# Testing_LAB_EMG_V1_2.net
KiCad netlist of a schematic drawn in EAGLE
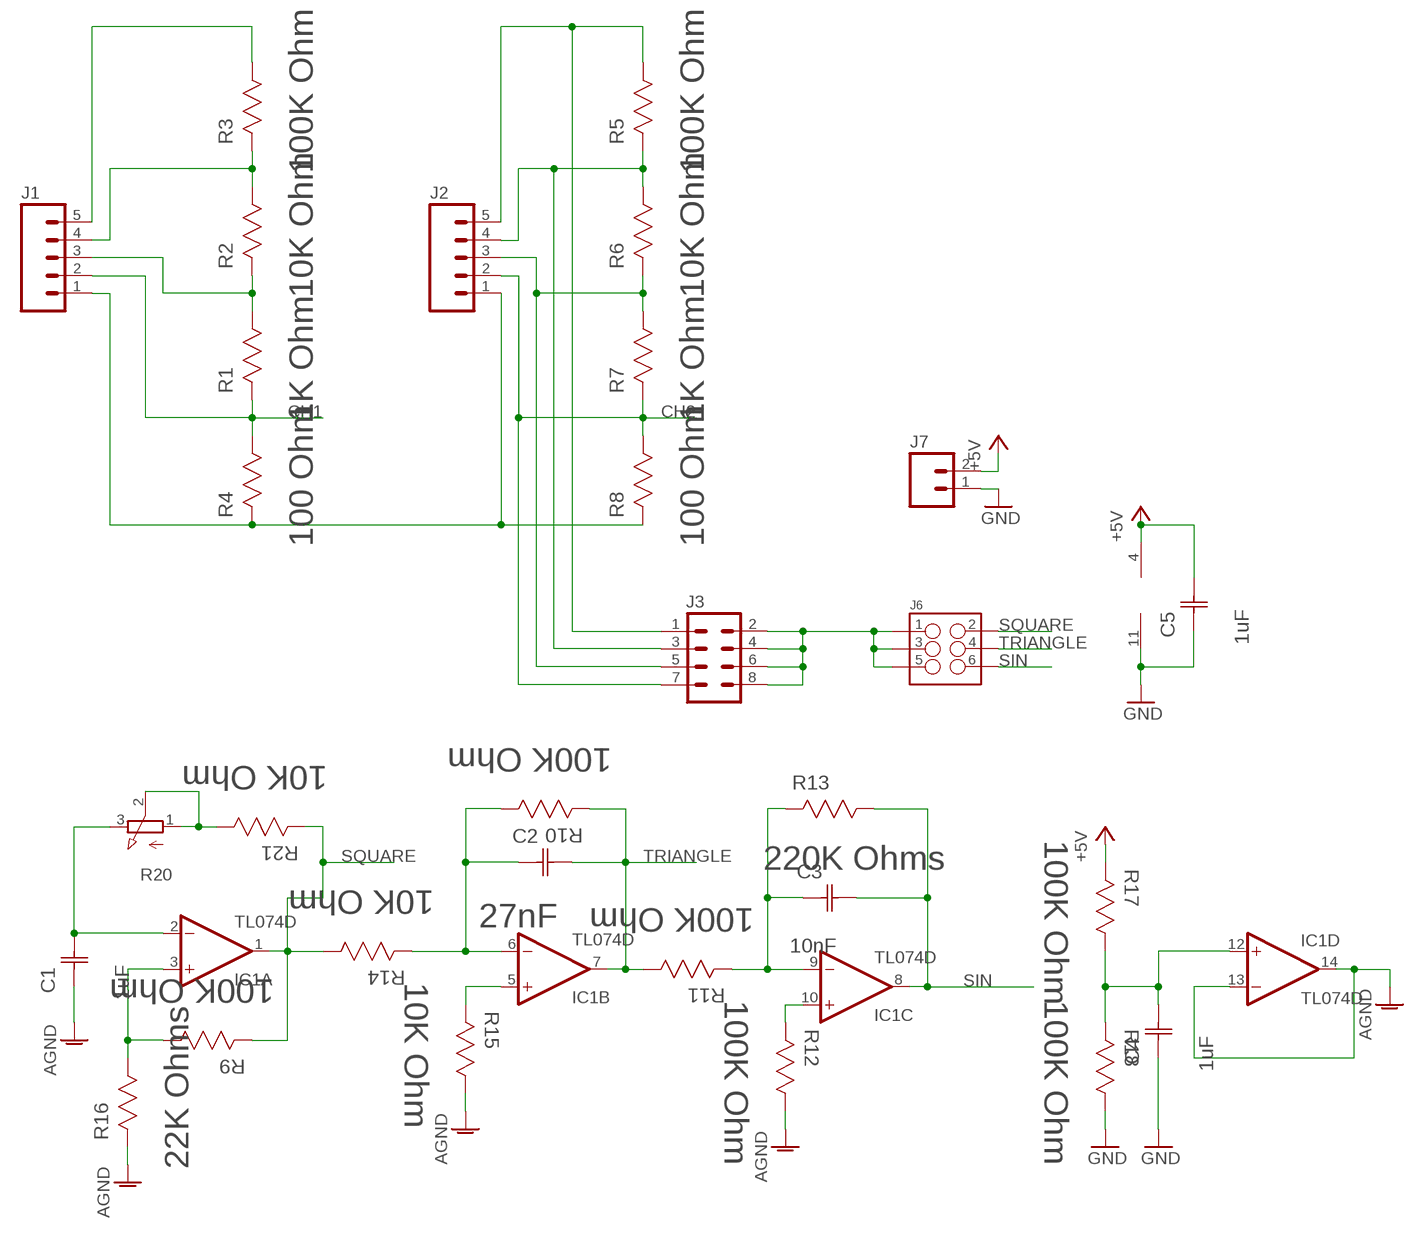
[diagram p0: schematic, sheet 1]

(export (version "E")
  (design (tool "Eeschema 10.0.6"))
  (components
    (comp (ref "C1")
      (value "1uF")
      (footprint "eagle-import:CAPC1608X94N")
      (fields (field (name "MPN") "0603YC105KAT2A") (field (name "TOLERANCE") "±10%"))
      (libsource (lib "eagle-import") (part "0603YC105KAT2A"))
    )
    (comp (ref "C2")
      (value "27nF")
      (footprint "eagle-import:CAPC1005X60N")
      (fields (field (name "MPN") "C0402C273K3RACTU") (field (name "TOLERANCE") "±10%"))
      (libsource (lib "eagle-import") (part "C0402C273K3RACTU"))
    )
    (comp (ref "C3")
      (value "10nF")
      (footprint "eagle-import:CAPC1608X90N")
      (fields (field (name "MPN") "06031C103KAT2A") (field (name "TOLERANCE") "±10%"))
      (libsource (lib "eagle-import") (part "06031C103KAT2A"))
    )
    (comp (ref "C4")
      (value "1uF")
      (footprint "eagle-import:CAPC1608X94N")
      (fields (field (name "MPN") "0603YC105KAT2A") (field (name "TOLERANCE") "±10%"))
      (libsource (lib "eagle-import") (part "0603YC105KAT2A"))
    )
    (comp (ref "C5")
      (value "1uF")
      (footprint "eagle-import:CAPC1608X94N")
      (fields (field (name "MPN") "0603YC105KAT2A") (field (name "TOLERANCE") "±10%"))
      (libsource (lib "eagle-import") (part "0603YC105KAT2A"))
    )
    (comp (ref "IC1")
      (value "TL074D")
      (footprint "eagle-import:SO14")
      (libsource (lib "eagle-import") (part "TL074D"))
    )
    (comp (ref "J1")
      (value "M05PTH")
      (footprint "eagle-import:1X05")
      (libsource (lib "eagle-import") (part "M05PTH"))
    )
    (comp (ref "J2")
      (value "M05PTH")
      (footprint "eagle-import:1X05")
      (libsource (lib "eagle-import") (part "M05PTH"))
    )
    (comp (ref "J3")
      (value "M04X2")
      (footprint "eagle-import:2X4")
      (libsource (lib "eagle-import") (part "M04X2"))
    )
    (comp (ref "J6")
      (value "M03X2NO_SILK")
      (footprint "eagle-import:2X3-NS")
      (libsource (lib "eagle-import") (part "M03X2NO_SILK"))
    )
    (comp (ref "J7")
      (value "M02PTH")
      (footprint "eagle-import:1X02")
      (libsource (lib "eagle-import") (part "M02PTH"))
    )
    (comp (ref "R1")
      (value "1K Ohm")
      (footprint "eagle-import:RESC1608X60N")
      (fields (field (name "MPN") "9C06031A1001FKHFT") (field (name "TOLERANCE") "±1%"))
      (libsource (lib "eagle-import") (part "9C06031A1001FKHFT"))
    )
    (comp (ref "R2")
      (value "10K Ohm")
      (footprint "eagle-import:RESC1608X60N")
      (fields (field (name "MPN") "9C06031A1002JLHFT") (field (name "TOLERANCE") "±5%"))
      (libsource (lib "eagle-import") (part "9C06031A1002JLHFT"))
    )
    (comp (ref "R3")
      (value "100K Ohm")
      (footprint "eagle-import:RESC1608X60N")
      (fields (field (name "MPN") "9C06031A1003FKHFT") (field (name "TOLERANCE") "±1%"))
      (libsource (lib "eagle-import") (part "9C06031A1003FKHFT"))
    )
    (comp (ref "R4")
      (value "100 Ohm")
      (footprint "eagle-import:RESC1608X60N")
      (fields (field (name "MPN") "9C06031A1000JLHFT") (field (name "TOLERANCE") "±5%"))
      (libsource (lib "eagle-import") (part "9C06031A1000JLHFT"))
    )
    (comp (ref "R5")
      (value "100K Ohm")
      (footprint "eagle-import:RESC1608X60N")
      (fields (field (name "MPN") "9C06031A1003FKHFT") (field (name "TOLERANCE") "±1%"))
      (libsource (lib "eagle-import") (part "9C06031A1003FKHFT"))
    )
    (comp (ref "R6")
      (value "10K Ohm")
      (footprint "eagle-import:RESC1608X60N")
      (fields (field (name "MPN") "9C06031A1002JLHFT") (field (name "TOLERANCE") "±5%"))
      (libsource (lib "eagle-import") (part "9C06031A1002JLHFT"))
    )
    (comp (ref "R7")
      (value "1K Ohm")
      (footprint "eagle-import:RESC1608X60N")
      (fields (field (name "MPN") "9C06031A1001FKHFT") (field (name "TOLERANCE") "±1%"))
      (libsource (lib "eagle-import") (part "9C06031A1001FKHFT"))
    )
    (comp (ref "R8")
      (value "100 Ohm")
      (footprint "eagle-import:RESC1608X60N")
      (fields (field (name "MPN") "9C06031A1000JLHFT") (field (name "TOLERANCE") "±5%"))
      (libsource (lib "eagle-import") (part "9C06031A1000JLHFT"))
    )
    (comp (ref "R9")
      (value "100K Ohm")
      (footprint "eagle-import:RESC1608X60N")
      (fields (field (name "MPN") "9C06031A1003FKHFT") (field (name "TOLERANCE") "±1%"))
      (libsource (lib "eagle-import") (part "9C06031A1003FKHFT"))
    )
    (comp (ref "R10")
      (value "100K Ohm")
      (footprint "eagle-import:RESC1608X60N")
      (fields (field (name "MPN") "9C06031A1003FKHFT") (field (name "TOLERANCE") "±1%"))
      (libsource (lib "eagle-import") (part "9C06031A1003FKHFT"))
    )
    (comp (ref "R11")
      (value "100K Ohm")
      (footprint "eagle-import:RESC1608X60N")
      (fields (field (name "MPN") "9C06031A1003FKHFT") (field (name "TOLERANCE") "±1%"))
      (libsource (lib "eagle-import") (part "9C06031A1003FKHFT"))
    )
    (comp (ref "R12")
      (value "100K Ohm")
      (footprint "eagle-import:RESC1608X60N")
      (fields (field (name "MPN") "9C06031A1003FKHFT") (field (name "TOLERANCE") "±1%"))
      (libsource (lib "eagle-import") (part "9C06031A1003FKHFT"))
    )
    (comp (ref "R13")
      (value "220K Ohms")
      (footprint "eagle-import:RESC1608X60N")
      (fields (field (name "MPN") "RC0603FR-07220KL") (field (name "TOLERANCE") "±1%"))
      (libsource (lib "eagle-import") (part "RC0603FR-07220KL"))
    )
    (comp (ref "R14")
      (value "10K Ohm")
      (footprint "eagle-import:RESC1608X60N")
      (fields (field (name "MPN") "9C06031A1002JLHFT") (field (name "TOLERANCE") "±5%"))
      (libsource (lib "eagle-import") (part "9C06031A1002JLHFT"))
    )
    (comp (ref "R15")
      (value "10K Ohm")
      (footprint "eagle-import:RESC1608X60N")
      (fields (field (name "MPN") "9C06031A1002JLHFT") (field (name "TOLERANCE") "±5%"))
      (libsource (lib "eagle-import") (part "9C06031A1002JLHFT"))
    )
    (comp (ref "R16")
      (value "22K Ohms")
      (footprint "eagle-import:RESC1608X60N")
      (fields (field (name "MPN") "RC0603FR-0722KL") (field (name "TOLERANCE") "±1%"))
      (libsource (lib "eagle-import") (part "RC0603FR-0722KL"))
    )
    (comp (ref "R17")
      (value "100K Ohm")
      (footprint "eagle-import:RESC1608X60N")
      (fields (field (name "MPN") "9C06031A1003FKHFT") (field (name "TOLERANCE") "±1%"))
      (libsource (lib "eagle-import") (part "9C06031A1003FKHFT"))
    )
    (comp (ref "R18")
      (value "100K Ohm")
      (footprint "eagle-import:RESC1608X60N")
      (fields (field (name "MPN") "9C06031A1003FKHFT") (field (name "TOLERANCE") "±1%"))
      (libsource (lib "eagle-import") (part "9C06031A1003FKHFT"))
    )
    (comp (ref "R20")
      (value "3RP/1610N")
      (footprint "eagle-import:3RP_1610N")
      (libsource (lib "eagle-import") (part "3RP/1610N"))
    )
    (comp (ref "R21")
      (value "10K Ohm")
      (footprint "eagle-import:RESC1608X60N")
      (fields (field (name "MPN") "9C06031A1002JLHFT") (field (name "TOLERANCE") "±5%"))
      (libsource (lib "eagle-import") (part "9C06031A1002JLHFT"))
    )
  )
  (nets
    (net (code "1") (name "+5V") (class "Default")
      (node (ref "C5") (pin "2") (pinfunction "C2_2") (pintype "passive"))
      (node (ref "IC1") (pin "4") (pinfunction "V+_4") (pintype "power_in"))
      (node (ref "J7") (pin "2") (pinfunction "2_2") (pintype "passive"))
      (node (ref "R17") (pin "2") (pinfunction "R2_2") (pintype "passive"))
    )
    (net (code "2") (name "/CH1") (class "Default")
      (node (ref "J1") (pin "2") (pinfunction "2_2") (pintype "passive"))
      (node (ref "R1") (pin "2") (pinfunction "R2_2") (pintype "passive"))
      (node (ref "R4") (pin "1") (pinfunction "R1_1") (pintype "passive"))
    )
    (net (code "3") (name "/CH2") (class "Default")
      (node (ref "J2") (pin "2") (pinfunction "2_2") (pintype "passive"))
      (node (ref "J3") (pin "7") (pinfunction "7_7") (pintype "passive"))
      (node (ref "R7") (pin "2") (pinfunction "R2_2") (pintype "passive"))
      (node (ref "R8") (pin "1") (pinfunction "R1_1") (pintype "passive"))
    )
    (net (code "4") (name "/SIN") (class "Default")
      (node (ref "C3") (pin "2") (pinfunction "C2_2") (pintype "passive"))
      (node (ref "IC1") (pin "8") (pinfunction "OUT_8") (pintype "output"))
      (node (ref "J6") (pin "6") (pinfunction "6_6") (pintype "bidirectional"))
      (node (ref "R13") (pin "1") (pinfunction "R1_1") (pintype "passive"))
    )
    (net (code "5") (name "/SQUARE") (class "Default")
      (node (ref "IC1") (pin "1") (pinfunction "OUT_1") (pintype "output"))
      (node (ref "J6") (pin "2") (pinfunction "2_2") (pintype "bidirectional"))
      (node (ref "R14") (pin "1") (pinfunction "R1_1") (pintype "passive"))
      (node (ref "R21") (pin "2") (pinfunction "R2_2") (pintype "passive"))
      (node (ref "R9") (pin "2") (pinfunction "R2_2") (pintype "passive"))
    )
    (net (code "6") (name "/TRIANGLE") (class "Default")
      (node (ref "C2") (pin "2") (pinfunction "C2_2") (pintype "passive"))
      (node (ref "IC1") (pin "7") (pinfunction "OUT_7") (pintype "output"))
      (node (ref "J6") (pin "4") (pinfunction "4_4") (pintype "bidirectional"))
      (node (ref "R10") (pin "2") (pinfunction "R2_2") (pintype "passive"))
      (node (ref "R11") (pin "1") (pinfunction "R1_1") (pintype "passive"))
    )
    (net (code "7") (name "AGND") (class "Default")
      (node (ref "C1") (pin "1") (pinfunction "C1_1") (pintype "passive"))
      (node (ref "IC1") (pin "13") (pinfunction "-IN_13") (pintype "input"))
      (node (ref "IC1") (pin "14") (pinfunction "OUT_14") (pintype "output"))
      (node (ref "R12") (pin "1") (pinfunction "R1_1") (pintype "passive"))
      (node (ref "R15") (pin "1") (pinfunction "R1_1") (pintype "passive"))
      (node (ref "R16") (pin "2") (pinfunction "R2_2") (pintype "passive"))
    )
    (net (code "8") (name "GND") (class "Default")
      (node (ref "C4") (pin "1") (pinfunction "C1_1") (pintype "passive"))
      (node (ref "C5") (pin "1") (pinfunction "C1_1") (pintype "passive"))
      (node (ref "IC1") (pin "11") (pinfunction "V-_11") (pintype "power_in"))
      (node (ref "J7") (pin "1") (pinfunction "1_1") (pintype "passive"))
      (node (ref "R18") (pin "1") (pinfunction "R1_1") (pintype "passive"))
    )
    (net (code "9") (name "Net-(C1-C2)") (class "Default")
      (node (ref "C1") (pin "2") (pinfunction "C2_2") (pintype "passive"))
      (node (ref "IC1") (pin "2") (pinfunction "-IN_2") (pintype "input"))
      (node (ref "R20") (pin "3") (pinfunction "E_3") (pintype "passive"))
    )
    (net (code "10") (name "Net-(C2-C1)") (class "Default")
      (node (ref "C2") (pin "1") (pinfunction "C1_1") (pintype "passive"))
      (node (ref "IC1") (pin "6") (pinfunction "-IN_6") (pintype "input"))
      (node (ref "R10") (pin "1") (pinfunction "R1_1") (pintype "passive"))
      (node (ref "R14") (pin "2") (pinfunction "R2_2") (pintype "passive"))
    )
    (net (code "11") (name "Net-(C3-C1)") (class "Default")
      (node (ref "C3") (pin "1") (pinfunction "C1_1") (pintype "passive"))
      (node (ref "IC1") (pin "9") (pinfunction "-IN_9") (pintype "input"))
      (node (ref "R11") (pin "2") (pinfunction "R2_2") (pintype "passive"))
      (node (ref "R13") (pin "2") (pinfunction "R2_2") (pintype "passive"))
    )
    (net (code "12") (name "Net-(C4-C2)") (class "Default")
      (node (ref "C4") (pin "2") (pinfunction "C2_2") (pintype "passive"))
      (node (ref "IC1") (pin "12") (pinfunction "+IN_12") (pintype "input"))
      (node (ref "R17") (pin "1") (pinfunction "R1_1") (pintype "passive"))
      (node (ref "R18") (pin "2") (pinfunction "R2_2") (pintype "passive"))
    )
    (net (code "13") (name "Net-(IC1A-+IN)") (class "Default")
      (node (ref "IC1") (pin "3") (pinfunction "+IN_3") (pintype "input"))
      (node (ref "R16") (pin "1") (pinfunction "R1_1") (pintype "passive"))
      (node (ref "R9") (pin "1") (pinfunction "R1_1") (pintype "passive"))
    )
    (net (code "14") (name "Net-(IC1B-+IN)") (class "Default")
      (node (ref "IC1") (pin "5") (pinfunction "+IN_5") (pintype "input"))
      (node (ref "R15") (pin "2") (pinfunction "R2_2") (pintype "passive"))
    )
    (net (code "15") (name "Net-(IC1C-+IN)") (class "Default")
      (node (ref "IC1") (pin "10") (pinfunction "+IN_10") (pintype "input"))
      (node (ref "R12") (pin "2") (pinfunction "R2_2") (pintype "passive"))
    )
    (net (code "16") (name "Net-(J3-Pad2)") (class "Default")
      (node (ref "J3") (pin "2") (pinfunction "2_2") (pintype "passive"))
      (node (ref "J3") (pin "4") (pinfunction "4_4") (pintype "passive"))
      (node (ref "J3") (pin "6") (pinfunction "6_6") (pintype "passive"))
      (node (ref "J3") (pin "8") (pinfunction "8_8") (pintype "passive"))
      (node (ref "J6") (pin "1") (pinfunction "1_1") (pintype "bidirectional"))
      (node (ref "J6") (pin "3") (pinfunction "3_3") (pintype "bidirectional"))
      (node (ref "J6") (pin "5") (pinfunction "5_5") (pintype "bidirectional"))
    )
    (net (code "17") (name "Net-(R1-R1)") (class "Default")
      (node (ref "J1") (pin "3") (pinfunction "3_3") (pintype "passive"))
      (node (ref "R1") (pin "1") (pinfunction "R1_1") (pintype "passive"))
      (node (ref "R2") (pin "2") (pinfunction "R2_2") (pintype "passive"))
    )
    (net (code "18") (name "Net-(R2-R1)") (class "Default")
      (node (ref "J1") (pin "4") (pinfunction "4_4") (pintype "passive"))
      (node (ref "R2") (pin "1") (pinfunction "R1_1") (pintype "passive"))
      (node (ref "R3") (pin "2") (pinfunction "R2_2") (pintype "passive"))
    )
    (net (code "19") (name "Net-(R3-R1)") (class "Default")
      (node (ref "J1") (pin "5") (pinfunction "5_5") (pintype "passive"))
      (node (ref "R3") (pin "1") (pinfunction "R1_1") (pintype "passive"))
    )
    (net (code "20") (name "Net-(R4-R2)") (class "Default")
      (node (ref "J1") (pin "1") (pinfunction "1_1") (pintype "passive"))
      (node (ref "J2") (pin "1") (pinfunction "1_1") (pintype "passive"))
      (node (ref "R4") (pin "2") (pinfunction "R2_2") (pintype "passive"))
      (node (ref "R8") (pin "2") (pinfunction "R2_2") (pintype "passive"))
    )
    (net (code "21") (name "Net-(R5-R1)") (class "Default")
      (node (ref "J2") (pin "5") (pinfunction "5_5") (pintype "passive"))
      (node (ref "J3") (pin "1") (pinfunction "1_1") (pintype "passive"))
      (node (ref "R5") (pin "1") (pinfunction "R1_1") (pintype "passive"))
    )
    (net (code "22") (name "Net-(R5-R2)") (class "Default")
      (node (ref "J2") (pin "4") (pinfunction "4_4") (pintype "passive"))
      (node (ref "J3") (pin "3") (pinfunction "3_3") (pintype "passive"))
      (node (ref "R5") (pin "2") (pinfunction "R2_2") (pintype "passive"))
      (node (ref "R6") (pin "1") (pinfunction "R1_1") (pintype "passive"))
    )
    (net (code "23") (name "Net-(R6-R2)") (class "Default")
      (node (ref "J2") (pin "3") (pinfunction "3_3") (pintype "passive"))
      (node (ref "J3") (pin "5") (pinfunction "5_5") (pintype "passive"))
      (node (ref "R6") (pin "2") (pinfunction "R2_2") (pintype "passive"))
      (node (ref "R7") (pin "1") (pinfunction "R1_1") (pintype "passive"))
    )
    (net (code "24") (name "Net-(R20-A)") (class "Default")
      (node (ref "R20") (pin "1") (pinfunction "A_1") (pintype "passive"))
      (node (ref "R20") (pin "2") (pinfunction "S_2") (pintype "passive"))
      (node (ref "R21") (pin "1") (pinfunction "R1_1") (pintype "passive"))
    )
  )
)
